# Sweet4x4_02.net
KiCad netlist of a schematic drawn in Altium Designer
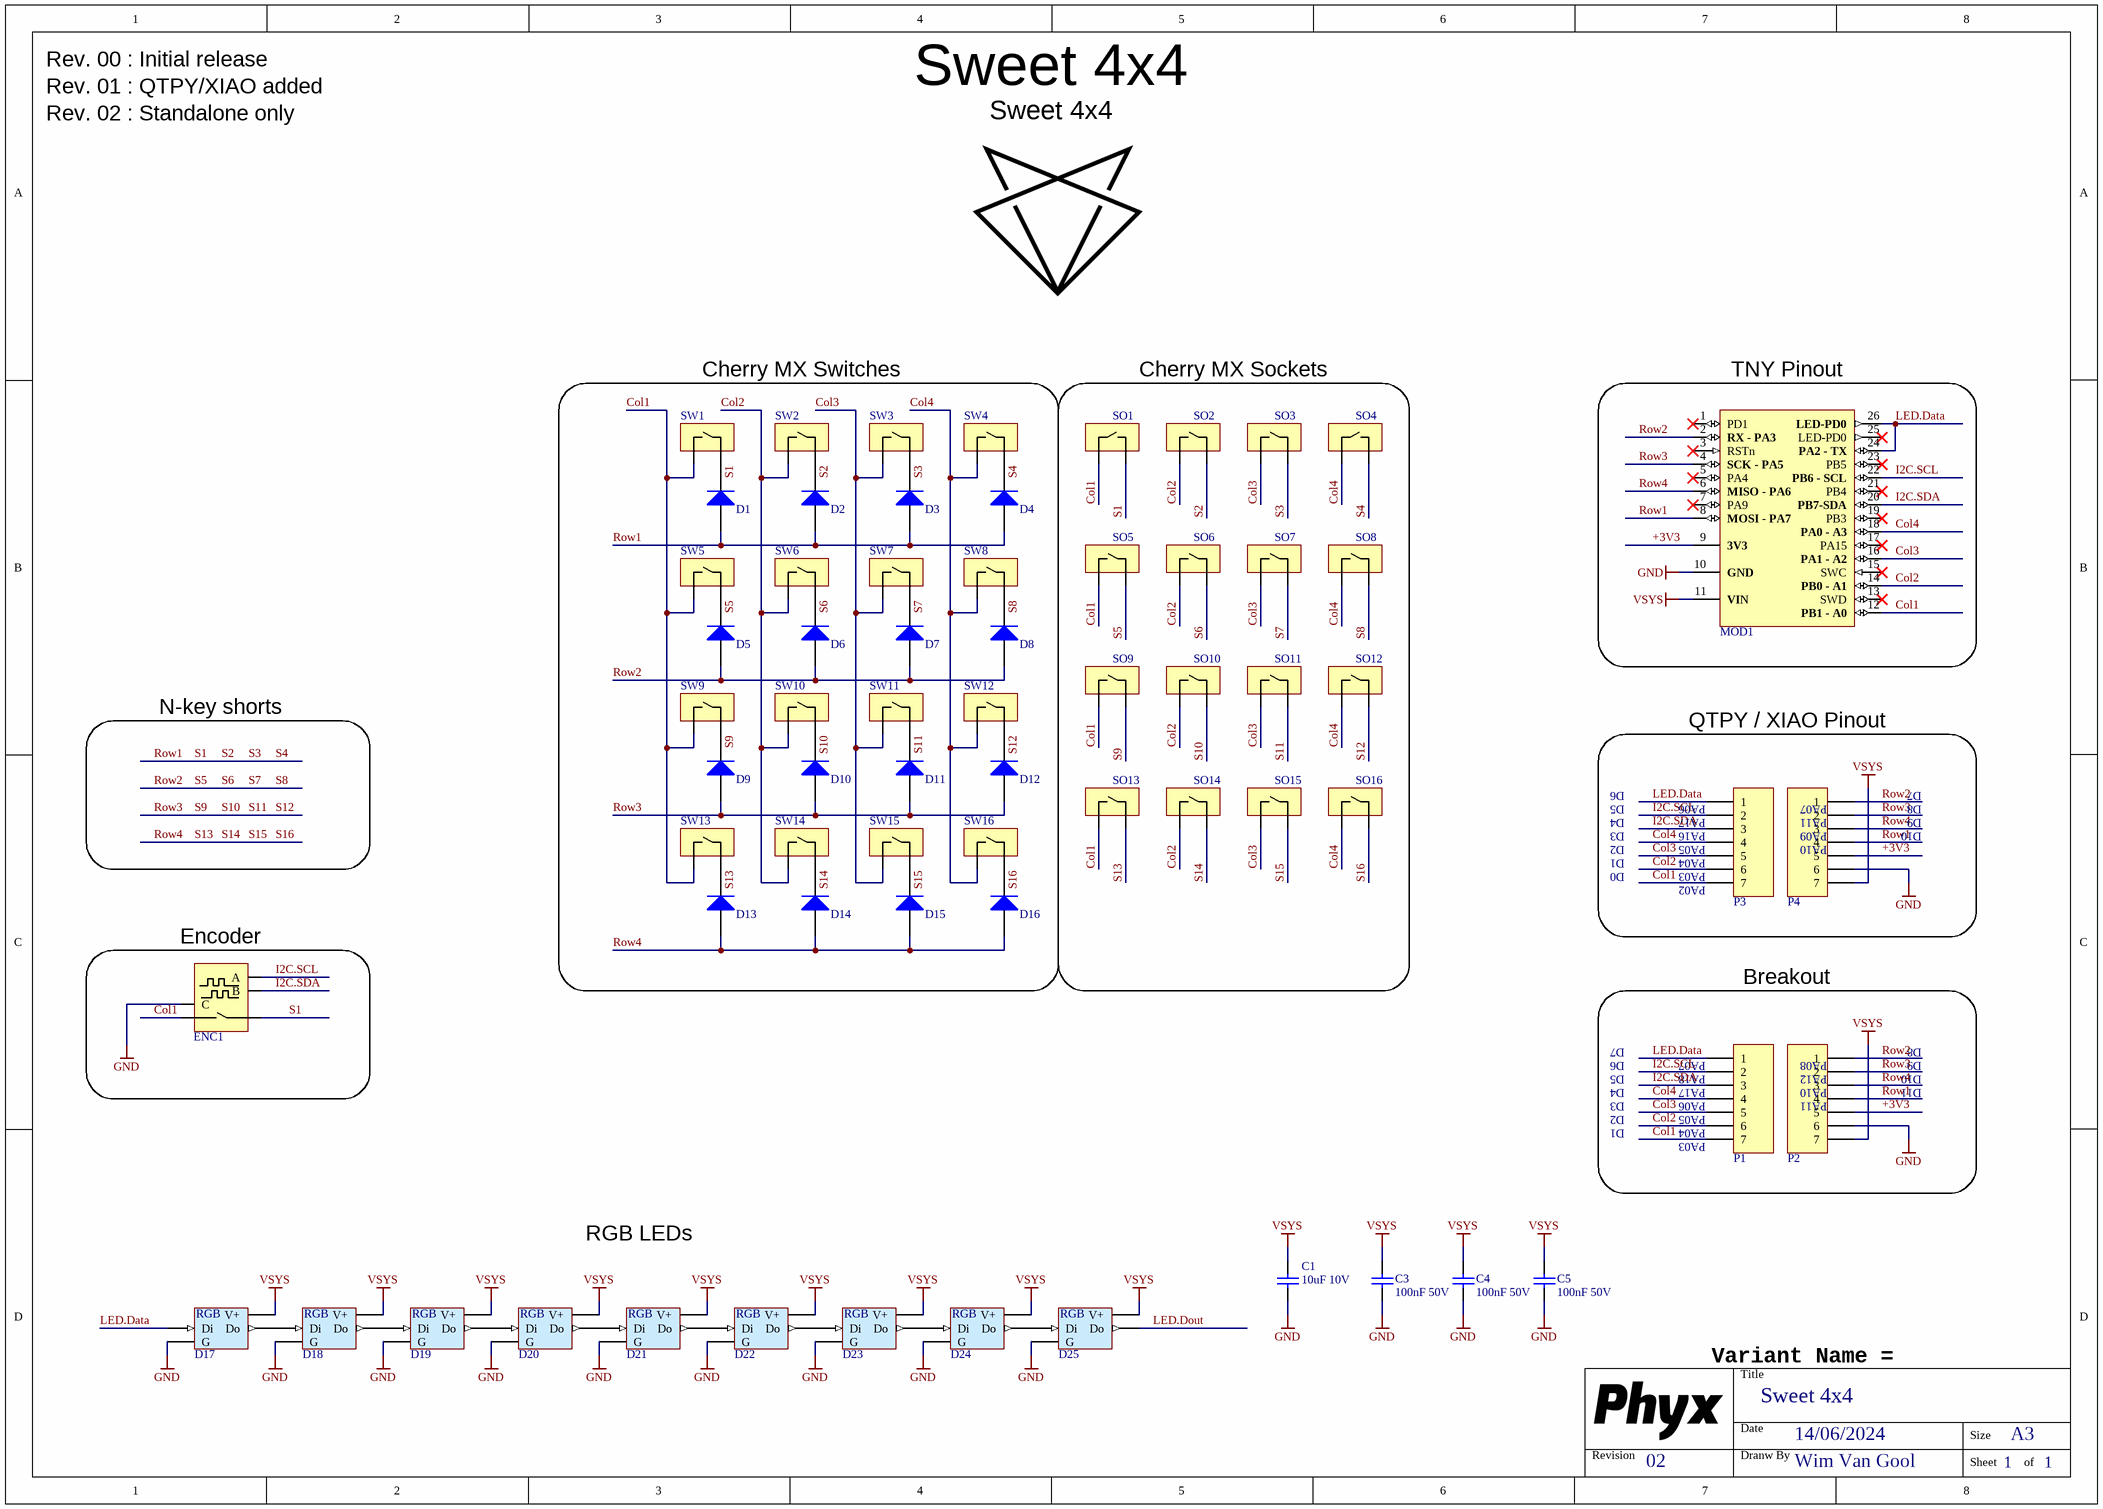
[diagram p0: Sweet4x4_02.SchDoc]

(export (version "E")
  (design (tool "Eeschema 10.0.6"))
  (components
    (comp (ref "C1")
      (value "10uF 10V")
      (footprint "C0805_N")
      (description "Capacitor Ceramic")
      (fields (field (name "Comment") "CAP_CERAMIC"))
      (libsource (lib "Phyx_Components") (part "CAP_CERAMIC"))
    )
    (comp (ref "C3")
      (value "100nF 50V")
      (footprint "C_5.08mm")
      (description "Capacitor Ceramic")
      (fields (field (name "Comment") "CAP_CERAMIC"))
      (libsource (lib "Phyx_Components") (part "CAP_CERAMIC"))
    )
    (comp (ref "C4")
      (value "100nF 50V")
      (footprint "C_5.08mm")
      (description "Capacitor Ceramic")
      (fields (field (name "Comment") "CAP_CERAMIC"))
      (libsource (lib "Phyx_Components") (part "CAP_CERAMIC"))
    )
    (comp (ref "C5")
      (value "100nF 50V")
      (footprint "C_5.08mm")
      (description "Capacitor Ceramic")
      (fields (field (name "Comment") "CAP_CERAMIC"))
      (libsource (lib "Phyx_Components") (part "CAP_CERAMIC"))
    )
    (comp (ref "D1")
      (value "1N4148 100V 200mA 1Vf@10mA")
      (footprint "DO-35")
      (description "Default Diode")
      (libsource (lib "Phyx_Components") (part "DIODE_AC"))
    )
    (comp (ref "D2")
      (value "1N4148 100V 200mA 1Vf@10mA")
      (footprint "DO-35")
      (description "Default Diode")
      (libsource (lib "Phyx_Components") (part "DIODE_AC"))
    )
    (comp (ref "D3")
      (value "1N4148 100V 200mA 1Vf@10mA")
      (footprint "DO-35")
      (description "Default Diode")
      (libsource (lib "Phyx_Components") (part "DIODE_AC"))
    )
    (comp (ref "D4")
      (value "1N4148 100V 200mA 1Vf@10mA")
      (footprint "DO-35")
      (description "Default Diode")
      (libsource (lib "Phyx_Components") (part "DIODE_AC"))
    )
    (comp (ref "D5")
      (value "1N4148 100V 200mA 1Vf@10mA")
      (footprint "DO-35")
      (description "Default Diode")
      (libsource (lib "Phyx_Components") (part "DIODE_AC"))
    )
    (comp (ref "D6")
      (value "1N4148 100V 200mA 1Vf@10mA")
      (footprint "DO-35")
      (description "Default Diode")
      (libsource (lib "Phyx_Components") (part "DIODE_AC"))
    )
    (comp (ref "D7")
      (value "1N4148 100V 200mA 1Vf@10mA")
      (footprint "DO-35")
      (description "Default Diode")
      (libsource (lib "Phyx_Components") (part "DIODE_AC"))
    )
    (comp (ref "D8")
      (value "1N4148 100V 200mA 1Vf@10mA")
      (footprint "DO-35")
      (description "Default Diode")
      (libsource (lib "Phyx_Components") (part "DIODE_AC"))
    )
    (comp (ref "D9")
      (value "1N4148 100V 200mA 1Vf@10mA")
      (footprint "DO-35")
      (description "Default Diode")
      (libsource (lib "Phyx_Components") (part "DIODE_AC"))
    )
    (comp (ref "D10")
      (value "1N4148 100V 200mA 1Vf@10mA")
      (footprint "DO-35")
      (description "Default Diode")
      (libsource (lib "Phyx_Components") (part "DIODE_AC"))
    )
    (comp (ref "D11")
      (value "1N4148 100V 200mA 1Vf@10mA")
      (footprint "DO-35")
      (description "Default Diode")
      (libsource (lib "Phyx_Components") (part "DIODE_AC"))
    )
    (comp (ref "D12")
      (value "1N4148 100V 200mA 1Vf@10mA")
      (footprint "DO-35")
      (description "Default Diode")
      (libsource (lib "Phyx_Components") (part "DIODE_AC"))
    )
    (comp (ref "D13")
      (value "1N4148 100V 200mA 1Vf@10mA")
      (footprint "DO-35")
      (description "Default Diode")
      (libsource (lib "Phyx_Components") (part "DIODE_AC"))
    )
    (comp (ref "D14")
      (value "1N4148 100V 200mA 1Vf@10mA")
      (footprint "DO-35")
      (description "Default Diode")
      (libsource (lib "Phyx_Components") (part "DIODE_AC"))
    )
    (comp (ref "D15")
      (value "1N4148 100V 200mA 1Vf@10mA")
      (footprint "DO-35")
      (description "Default Diode")
      (libsource (lib "Phyx_Components") (part "DIODE_AC"))
    )
    (comp (ref "D16")
      (value "1N4148 100V 200mA 1Vf@10mA")
      (footprint "DO-35")
      (description "Default Diode")
      (libsource (lib "Phyx_Components") (part "DIODE_AC"))
    )
    (comp (ref "D17")
      (value "WS2812 based digital RGB LED 5mm Rectangle")
      (footprint "LED_5mm_RGB_RECT_EASY")
      (description "LED RGB WS2812 5mm Rectangle")
      (libsource (lib "Phyx_Components") (part "LED_RGB_WS2812B_5mm"))
    )
    (comp (ref "D18")
      (value "WS2812 based digital RGB LED 5mm Rectangle")
      (footprint "LED_5mm_RGB_RECT_EASY")
      (description "LED RGB WS2812 5mm Rectangle")
      (libsource (lib "Phyx_Components") (part "LED_RGB_WS2812B_5mm"))
    )
    (comp (ref "D19")
      (value "WS2812 based digital RGB LED 5mm Rectangle")
      (footprint "LED_5mm_RGB_RECT_EASY")
      (description "LED RGB WS2812 5mm Rectangle")
      (libsource (lib "Phyx_Components") (part "LED_RGB_WS2812B_5mm"))
    )
    (comp (ref "D20")
      (value "WS2812 based digital RGB LED 5mm Rectangle")
      (footprint "LED_5mm_RGB_RECT_EASY")
      (description "LED RGB WS2812 5mm Rectangle")
      (libsource (lib "Phyx_Components") (part "LED_RGB_WS2812B_5mm"))
    )
    (comp (ref "D21")
      (value "WS2812 based digital RGB LED 5mm Rectangle")
      (footprint "LED_5mm_RGB_RECT_EASY")
      (description "LED RGB WS2812 5mm Rectangle")
      (libsource (lib "Phyx_Components") (part "LED_RGB_WS2812B_5mm"))
    )
    (comp (ref "D22")
      (value "WS2812 based digital RGB LED 5mm Rectangle")
      (footprint "LED_5mm_RGB_RECT_EASY")
      (description "LED RGB WS2812 5mm Rectangle")
      (libsource (lib "Phyx_Components") (part "LED_RGB_WS2812B_5mm"))
    )
    (comp (ref "D23")
      (value "WS2812 based digital RGB LED 5mm Rectangle")
      (footprint "LED_5mm_RGB_RECT_EASY")
      (description "LED RGB WS2812 5mm Rectangle")
      (libsource (lib "Phyx_Components") (part "LED_RGB_WS2812B_5mm"))
    )
    (comp (ref "D24")
      (value "WS2812 based digital RGB LED 5mm Rectangle")
      (footprint "LED_5mm_RGB_RECT_EASY")
      (description "LED RGB WS2812 5mm Rectangle")
      (libsource (lib "Phyx_Components") (part "LED_RGB_WS2812B_5mm"))
    )
    (comp (ref "D25")
      (value "WS2812 based digital RGB LED 5mm Rectangle")
      (footprint "LED_5mm_RGB_RECT_EASY")
      (description "LED RGB WS2812 5mm Rectangle")
      (libsource (lib "Phyx_Components") (part "LED_RGB_WS2812B_5mm"))
    )
    (comp (ref "ENC1")
      (value "Rotary Encoder with Switch")
      (footprint "PEC11-4215F-S0024")
      (libsource (lib "Phyx_Components") (part "ROT_ENC_3P_SW"))
    )
    (comp (ref "MOD1")
      (value "CH23V203 based TNY module")
      (footprint "PHYX_LANA_TNY_SMD")
      (libsource (lib "Phyx_Components") (part "PHYX_LANA_TNY_SMD"))
    )
    (comp (ref "P1") (value "Header 7") (footprint "HDR1X7") (libsource (lib "") (part "Header 7_1")))
    (comp (ref "P2")
      (value "Header 7")
      (footprint "HDR1X7")
      (libsource (lib "Phyx_Components") (part "Header 7"))
    )
    (comp (ref "P3") (value "Header 7") (footprint "HDR1X7") (libsource (lib "") (part "Header 7_1")))
    (comp (ref "P4")
      (value "Header 7")
      (footprint "HDR1X7")
      (libsource (lib "Phyx_Components") (part "Header 7"))
    )
    (comp (ref "SO1")
      (value "Kailh MX Socket")
      (footprint "Kailh_MX_Socket")
      (libsource (lib "Phyx_Components") (part "SW_TACT"))
    )
    (comp (ref "SO2")
      (value "Kailh MX Socket")
      (footprint "Kailh_MX_Socket")
      (libsource (lib "") (part "SW_TACT_1"))
    )
    (comp (ref "SO3")
      (value "Kailh MX Socket")
      (footprint "Kailh_MX_Socket")
      (libsource (lib "") (part "SW_TACT_1"))
    )
    (comp (ref "SO4")
      (value "Kailh MX Socket")
      (footprint "Kailh_MX_Socket")
      (libsource (lib "Phyx_Components") (part "SW_TACT"))
    )
    (comp (ref "SO5")
      (value "Kailh MX Socket")
      (footprint "Kailh_MX_Socket")
      (libsource (lib "") (part "SW_TACT_1"))
    )
    (comp (ref "SO6")
      (value "Kailh MX Socket")
      (footprint "Kailh_MX_Socket")
      (libsource (lib "") (part "SW_TACT_1"))
    )
    (comp (ref "SO7")
      (value "Kailh MX Socket")
      (footprint "Kailh_MX_Socket")
      (libsource (lib "") (part "SW_TACT_1"))
    )
    (comp (ref "SO8")
      (value "Kailh MX Socket")
      (footprint "Kailh_MX_Socket")
      (libsource (lib "") (part "SW_TACT_1"))
    )
    (comp (ref "SO9")
      (value "Kailh MX Socket")
      (footprint "Kailh_MX_Socket")
      (libsource (lib "") (part "SW_TACT_1"))
    )
    (comp (ref "SO10")
      (value "Kailh MX Socket")
      (footprint "Kailh_MX_Socket")
      (libsource (lib "") (part "SW_TACT_1"))
    )
    (comp (ref "SO11")
      (value "Kailh MX Socket")
      (footprint "Kailh_MX_Socket")
      (libsource (lib "") (part "SW_TACT_1"))
    )
    (comp (ref "SO12")
      (value "Kailh MX Socket")
      (footprint "Kailh_MX_Socket")
      (libsource (lib "") (part "SW_TACT_1"))
    )
    (comp (ref "SO13")
      (value "Kailh MX Socket")
      (footprint "Kailh_MX_Socket")
      (libsource (lib "") (part "SW_TACT_1"))
    )
    (comp (ref "SO14")
      (value "Kailh MX Socket")
      (footprint "Kailh_MX_Socket")
      (libsource (lib "") (part "SW_TACT_1"))
    )
    (comp (ref "SO15")
      (value "Kailh MX Socket")
      (footprint "Kailh_MX_Socket")
      (libsource (lib "") (part "SW_TACT_1"))
    )
    (comp (ref "SO16")
      (value "Kailh MX Socket")
      (footprint "Kailh_MX_Socket")
      (libsource (lib "") (part "SW_TACT_1"))
    )
    (comp (ref "SW1")
      (value "Cherry MX Blue")
      (footprint "Cherry_MX1A")
      (libsource (lib "") (part "SW_TACT_1"))
    )
    (comp (ref "SW2")
      (value "Cherry MX Blue")
      (footprint "Cherry_MX1A")
      (libsource (lib "") (part "SW_TACT_1"))
    )
    (comp (ref "SW3")
      (value "Cherry MX Blue")
      (footprint "Cherry_MX1A")
      (libsource (lib "") (part "SW_TACT_1"))
    )
    (comp (ref "SW4")
      (value "Cherry MX Blue")
      (footprint "Cherry_MX1A")
      (libsource (lib "") (part "SW_TACT_1"))
    )
    (comp (ref "SW5")
      (value "Cherry MX Blue")
      (footprint "Cherry_MX1A")
      (libsource (lib "") (part "SW_TACT_1"))
    )
    (comp (ref "SW6")
      (value "Cherry MX Blue")
      (footprint "Cherry_MX1A")
      (libsource (lib "") (part "SW_TACT_1"))
    )
    (comp (ref "SW7")
      (value "Cherry MX Blue")
      (footprint "Cherry_MX1A")
      (libsource (lib "") (part "SW_TACT_1"))
    )
    (comp (ref "SW8")
      (value "Cherry MX Blue")
      (footprint "Cherry_MX1A")
      (libsource (lib "") (part "SW_TACT_1"))
    )
    (comp (ref "SW9")
      (value "Cherry MX Blue")
      (footprint "Cherry_MX1A")
      (libsource (lib "") (part "SW_TACT_1"))
    )
    (comp (ref "SW10")
      (value "Cherry MX Blue")
      (footprint "Cherry_MX1A")
      (libsource (lib "") (part "SW_TACT_1"))
    )
    (comp (ref "SW11")
      (value "Cherry MX Blue")
      (footprint "Cherry_MX1A")
      (libsource (lib "") (part "SW_TACT_1"))
    )
    (comp (ref "SW12")
      (value "Cherry MX Blue")
      (footprint "Cherry_MX1A")
      (libsource (lib "") (part "SW_TACT_1"))
    )
    (comp (ref "SW13")
      (value "Cherry MX Blue")
      (footprint "Cherry_MX1A")
      (libsource (lib "") (part "SW_TACT_1"))
    )
    (comp (ref "SW14")
      (value "Cherry MX Blue")
      (footprint "Cherry_MX1A")
      (libsource (lib "") (part "SW_TACT_1"))
    )
    (comp (ref "SW15")
      (value "Cherry MX Blue")
      (footprint "Cherry_MX1A")
      (libsource (lib "") (part "SW_TACT_1"))
    )
    (comp (ref "SW16")
      (value "Cherry MX Blue")
      (footprint "Cherry_MX1A")
      (libsource (lib "") (part "SW_TACT_1"))
    )
  )
  (nets
    (net (code "1") (name "/+3V3") (class "Default")
      (node (ref "MOD1") (pin "9") (pinfunction "3V3_9") (pintype "power_in"))
      (node (ref "P2") (pin "5") (pinfunction "5_5") (pintype "passive"))
      (node (ref "P4") (pin "5") (pinfunction "5_5") (pintype "passive"))
    )
    (net (code "2") (name "/Col1") (class "Default")
      (node (ref "ENC1") (pin "1") (pinfunction "1_1") (pintype "passive"))
      (node (ref "MOD1") (pin "12") (pinfunction "PB1_-_A0_12") (pintype "bidirectional"))
      (node (ref "P1") (pin "7") (pinfunction "7_7") (pintype "passive"))
      (node (ref "P3") (pin "7") (pinfunction "7_7") (pintype "passive"))
      (node (ref "SO1") (pin "2") (pinfunction "2_2") (pintype "passive"))
      (node (ref "SO13") (pin "1") (pinfunction "1_1") (pintype "passive"))
      (node (ref "SO5") (pin "1") (pinfunction "1_1") (pintype "passive"))
      (node (ref "SO9") (pin "1") (pinfunction "1_1") (pintype "passive"))
      (node (ref "SW1") (pin "1") (pinfunction "1_1") (pintype "passive"))
      (node (ref "SW13") (pin "1") (pinfunction "1_1") (pintype "passive"))
      (node (ref "SW5") (pin "1") (pinfunction "1_1") (pintype "passive"))
      (node (ref "SW9") (pin "1") (pinfunction "1_1") (pintype "passive"))
    )
    (net (code "3") (name "/Col2") (class "Default")
      (node (ref "MOD1") (pin "14") (pinfunction "PB0_-_A1_14") (pintype "bidirectional"))
      (node (ref "P1") (pin "6") (pinfunction "6_6") (pintype "passive"))
      (node (ref "P3") (pin "6") (pinfunction "6_6") (pintype "passive"))
      (node (ref "SO10") (pin "1") (pinfunction "1_1") (pintype "passive"))
      (node (ref "SO14") (pin "1") (pinfunction "1_1") (pintype "passive"))
      (node (ref "SO2") (pin "1") (pinfunction "1_1") (pintype "passive"))
      (node (ref "SO6") (pin "1") (pinfunction "1_1") (pintype "passive"))
      (node (ref "SW10") (pin "1") (pinfunction "1_1") (pintype "passive"))
      (node (ref "SW14") (pin "1") (pinfunction "1_1") (pintype "passive"))
      (node (ref "SW2") (pin "1") (pinfunction "1_1") (pintype "passive"))
      (node (ref "SW6") (pin "1") (pinfunction "1_1") (pintype "passive"))
    )
    (net (code "4") (name "/Col3") (class "Default")
      (node (ref "MOD1") (pin "16") (pinfunction "PA1_-_A2_16") (pintype "bidirectional"))
      (node (ref "P1") (pin "5") (pinfunction "5_5") (pintype "passive"))
      (node (ref "P3") (pin "5") (pinfunction "5_5") (pintype "passive"))
      (node (ref "SO11") (pin "1") (pinfunction "1_1") (pintype "passive"))
      (node (ref "SO15") (pin "1") (pinfunction "1_1") (pintype "passive"))
      (node (ref "SO3") (pin "1") (pinfunction "1_1") (pintype "passive"))
      (node (ref "SO7") (pin "1") (pinfunction "1_1") (pintype "passive"))
      (node (ref "SW11") (pin "1") (pinfunction "1_1") (pintype "passive"))
      (node (ref "SW15") (pin "1") (pinfunction "1_1") (pintype "passive"))
      (node (ref "SW3") (pin "1") (pinfunction "1_1") (pintype "passive"))
      (node (ref "SW7") (pin "1") (pinfunction "1_1") (pintype "passive"))
    )
    (net (code "5") (name "/Col4") (class "Default")
      (node (ref "MOD1") (pin "18") (pinfunction "PA0_-_A3_18") (pintype "bidirectional"))
      (node (ref "P1") (pin "4") (pinfunction "4_4") (pintype "passive"))
      (node (ref "P3") (pin "4") (pinfunction "4_4") (pintype "passive"))
      (node (ref "SO12") (pin "1") (pinfunction "1_1") (pintype "passive"))
      (node (ref "SO16") (pin "1") (pinfunction "1_1") (pintype "passive"))
      (node (ref "SO4") (pin "2") (pinfunction "2_2") (pintype "passive"))
      (node (ref "SO8") (pin "1") (pinfunction "1_1") (pintype "passive"))
      (node (ref "SW12") (pin "1") (pinfunction "1_1") (pintype "passive"))
      (node (ref "SW16") (pin "1") (pinfunction "1_1") (pintype "passive"))
      (node (ref "SW4") (pin "1") (pinfunction "1_1") (pintype "passive"))
      (node (ref "SW8") (pin "1") (pinfunction "1_1") (pintype "passive"))
    )
    (net (code "6") (name "/I2C.SCL") (class "Default")
      (node (ref "ENC1") (pin "A") (pinfunction "A_A") (pintype "passive"))
      (node (ref "MOD1") (pin "22") (pinfunction "PB6_-_SCL_22") (pintype "bidirectional"))
      (node (ref "P1") (pin "2") (pinfunction "2_2") (pintype "passive"))
      (node (ref "P3") (pin "2") (pinfunction "2_2") (pintype "passive"))
    )
    (net (code "7") (name "/I2C.SDA") (class "Default")
      (node (ref "ENC1") (pin "B") (pinfunction "B_B") (pintype "passive"))
      (node (ref "MOD1") (pin "20") (pinfunction "PB7-SDA_20") (pintype "bidirectional"))
      (node (ref "P1") (pin "3") (pinfunction "3_3") (pintype "passive"))
      (node (ref "P3") (pin "3") (pinfunction "3_3") (pintype "passive"))
    )
    (net (code "8") (name "/LED.Data") (class "Default")
      (node (ref "D17") (pin "4") (pinfunction "Di_4") (pintype "input"))
      (node (ref "MOD1") (pin "24") (pinfunction "PA2_-_TX_24") (pintype "bidirectional"))
      (node (ref "MOD1") (pin "26") (pinfunction "LED-PD0_26") (pintype "output"))
      (node (ref "P1") (pin "1") (pinfunction "1_1") (pintype "passive"))
      (node (ref "P3") (pin "1") (pinfunction "1_1") (pintype "passive"))
    )
    (net (code "9") (name "/LED.Dout") (class "Default")
      (node (ref "D25") (pin "1") (pinfunction "Do_1") (pintype "output"))
    )
    (net (code "10") (name "/Row1") (class "Default")
      (node (ref "D1") (pin "A") (pinfunction "A_A") (pintype "passive"))
      (node (ref "D1") (pin "C") (pinfunction "C_C") (pintype "passive"))
      (node (ref "D2") (pin "A") (pinfunction "A_A") (pintype "passive"))
      (node (ref "D2") (pin "C") (pinfunction "C_C") (pintype "passive"))
      (node (ref "D3") (pin "A") (pinfunction "A_A") (pintype "passive"))
      (node (ref "D3") (pin "C") (pinfunction "C_C") (pintype "passive"))
      (node (ref "D4") (pin "A") (pinfunction "A_A") (pintype "passive"))
      (node (ref "D4") (pin "C") (pinfunction "C_C") (pintype "passive"))
      (node (ref "ENC1") (pin "2") (pinfunction "2_2") (pintype "passive"))
      (node (ref "MOD1") (pin "8") (pinfunction "MOSI_-_PA7_8") (pintype "bidirectional"))
      (node (ref "P2") (pin "4") (pinfunction "4_4") (pintype "passive"))
      (node (ref "P4") (pin "4") (pinfunction "4_4") (pintype "passive"))
      (node (ref "SO1") (pin "1") (pinfunction "1_1") (pintype "passive"))
      (node (ref "SO2") (pin "2") (pinfunction "2_2") (pintype "passive"))
      (node (ref "SO3") (pin "2") (pinfunction "2_2") (pintype "passive"))
      (node (ref "SO4") (pin "1") (pinfunction "1_1") (pintype "passive"))
      (node (ref "SW1") (pin "2") (pinfunction "2_2") (pintype "passive"))
      (node (ref "SW2") (pin "2") (pinfunction "2_2") (pintype "passive"))
      (node (ref "SW3") (pin "2") (pinfunction "2_2") (pintype "passive"))
      (node (ref "SW4") (pin "2") (pinfunction "2_2") (pintype "passive"))
    )
    (net (code "11") (name "/Row2") (class "Default")
      (node (ref "D5") (pin "A") (pinfunction "A_A") (pintype "passive"))
      (node (ref "D5") (pin "C") (pinfunction "C_C") (pintype "passive"))
      (node (ref "D6") (pin "A") (pinfunction "A_A") (pintype "passive"))
      (node (ref "D6") (pin "C") (pinfunction "C_C") (pintype "passive"))
      (node (ref "D7") (pin "A") (pinfunction "A_A") (pintype "passive"))
      (node (ref "D7") (pin "C") (pinfunction "C_C") (pintype "passive"))
      (node (ref "D8") (pin "A") (pinfunction "A_A") (pintype "passive"))
      (node (ref "D8") (pin "C") (pinfunction "C_C") (pintype "passive"))
      (node (ref "MOD1") (pin "2") (pinfunction "RX_-_PA3_2") (pintype "bidirectional"))
      (node (ref "P2") (pin "1") (pinfunction "1_1") (pintype "passive"))
      (node (ref "P4") (pin "1") (pinfunction "1_1") (pintype "passive"))
      (node (ref "SO5") (pin "2") (pinfunction "2_2") (pintype "passive"))
      (node (ref "SO6") (pin "2") (pinfunction "2_2") (pintype "passive"))
      (node (ref "SO7") (pin "2") (pinfunction "2_2") (pintype "passive"))
      (node (ref "SO8") (pin "2") (pinfunction "2_2") (pintype "passive"))
      (node (ref "SW5") (pin "2") (pinfunction "2_2") (pintype "passive"))
      (node (ref "SW6") (pin "2") (pinfunction "2_2") (pintype "passive"))
      (node (ref "SW7") (pin "2") (pinfunction "2_2") (pintype "passive"))
      (node (ref "SW8") (pin "2") (pinfunction "2_2") (pintype "passive"))
    )
    (net (code "12") (name "/Row3") (class "Default")
      (node (ref "D10") (pin "A") (pinfunction "A_A") (pintype "passive"))
      (node (ref "D10") (pin "C") (pinfunction "C_C") (pintype "passive"))
      (node (ref "D11") (pin "A") (pinfunction "A_A") (pintype "passive"))
      (node (ref "D11") (pin "C") (pinfunction "C_C") (pintype "passive"))
      (node (ref "D12") (pin "A") (pinfunction "A_A") (pintype "passive"))
      (node (ref "D12") (pin "C") (pinfunction "C_C") (pintype "passive"))
      (node (ref "D9") (pin "A") (pinfunction "A_A") (pintype "passive"))
      (node (ref "D9") (pin "C") (pinfunction "C_C") (pintype "passive"))
      (node (ref "MOD1") (pin "4") (pinfunction "SCK_-_PA5_4") (pintype "bidirectional"))
      (node (ref "P2") (pin "2") (pinfunction "2_2") (pintype "passive"))
      (node (ref "P4") (pin "2") (pinfunction "2_2") (pintype "passive"))
      (node (ref "SO10") (pin "2") (pinfunction "2_2") (pintype "passive"))
      (node (ref "SO11") (pin "2") (pinfunction "2_2") (pintype "passive"))
      (node (ref "SO12") (pin "2") (pinfunction "2_2") (pintype "passive"))
      (node (ref "SO9") (pin "2") (pinfunction "2_2") (pintype "passive"))
      (node (ref "SW10") (pin "2") (pinfunction "2_2") (pintype "passive"))
      (node (ref "SW11") (pin "2") (pinfunction "2_2") (pintype "passive"))
      (node (ref "SW12") (pin "2") (pinfunction "2_2") (pintype "passive"))
      (node (ref "SW9") (pin "2") (pinfunction "2_2") (pintype "passive"))
    )
    (net (code "13") (name "/Row4") (class "Default")
      (node (ref "D13") (pin "A") (pinfunction "A_A") (pintype "passive"))
      (node (ref "D13") (pin "C") (pinfunction "C_C") (pintype "passive"))
      (node (ref "D14") (pin "A") (pinfunction "A_A") (pintype "passive"))
      (node (ref "D14") (pin "C") (pinfunction "C_C") (pintype "passive"))
      (node (ref "D15") (pin "A") (pinfunction "A_A") (pintype "passive"))
      (node (ref "D15") (pin "C") (pinfunction "C_C") (pintype "passive"))
      (node (ref "D16") (pin "A") (pinfunction "A_A") (pintype "passive"))
      (node (ref "D16") (pin "C") (pinfunction "C_C") (pintype "passive"))
      (node (ref "MOD1") (pin "6") (pinfunction "MISO_-_PA6_6") (pintype "bidirectional"))
      (node (ref "P2") (pin "3") (pinfunction "3_3") (pintype "passive"))
      (node (ref "P4") (pin "3") (pinfunction "3_3") (pintype "passive"))
      (node (ref "SO13") (pin "2") (pinfunction "2_2") (pintype "passive"))
      (node (ref "SO14") (pin "2") (pinfunction "2_2") (pintype "passive"))
      (node (ref "SO15") (pin "2") (pinfunction "2_2") (pintype "passive"))
      (node (ref "SO16") (pin "2") (pinfunction "2_2") (pintype "passive"))
      (node (ref "SW13") (pin "2") (pinfunction "2_2") (pintype "passive"))
      (node (ref "SW14") (pin "2") (pinfunction "2_2") (pintype "passive"))
      (node (ref "SW15") (pin "2") (pinfunction "2_2") (pintype "passive"))
      (node (ref "SW16") (pin "2") (pinfunction "2_2") (pintype "passive"))
    )
    (net (code "14") (name "GND") (class "Default")
      (node (ref "C1") (pin "2") (pinfunction "2_2") (pintype "passive"))
      (node (ref "C3") (pin "2") (pinfunction "2_2") (pintype "passive"))
      (node (ref "C4") (pin "2") (pinfunction "2_2") (pintype "passive"))
      (node (ref "C5") (pin "2") (pinfunction "2_2") (pintype "passive"))
      (node (ref "D17") (pin "3") (pinfunction "G_3") (pintype "power_in"))
      (node (ref "D18") (pin "3") (pinfunction "G_3") (pintype "power_in"))
      (node (ref "D19") (pin "3") (pinfunction "G_3") (pintype "power_in"))
      (node (ref "D20") (pin "3") (pinfunction "G_3") (pintype "power_in"))
      (node (ref "D21") (pin "3") (pinfunction "G_3") (pintype "power_in"))
      (node (ref "D22") (pin "3") (pinfunction "G_3") (pintype "power_in"))
      (node (ref "D23") (pin "3") (pinfunction "G_3") (pintype "power_in"))
      (node (ref "D24") (pin "3") (pinfunction "G_3") (pintype "power_in"))
      (node (ref "D25") (pin "3") (pinfunction "G_3") (pintype "power_in"))
      (node (ref "ENC1") (pin "C") (pinfunction "C_C") (pintype "passive"))
      (node (ref "MOD1") (pin "10") (pinfunction "GND_10") (pintype "power_in"))
      (node (ref "P2") (pin "6") (pinfunction "6_6") (pintype "passive"))
      (node (ref "P4") (pin "6") (pinfunction "6_6") (pintype "passive"))
    )
    (net (code "15") (name "Net-(D17-Do)") (class "Default")
      (node (ref "D17") (pin "1") (pinfunction "Do_1") (pintype "output"))
      (node (ref "D18") (pin "4") (pinfunction "Di_4") (pintype "input"))
    )
    (net (code "16") (name "Net-(D18-Do)") (class "Default")
      (node (ref "D18") (pin "1") (pinfunction "Do_1") (pintype "output"))
      (node (ref "D19") (pin "4") (pinfunction "Di_4") (pintype "input"))
    )
    (net (code "17") (name "Net-(D19-Do)") (class "Default")
      (node (ref "D19") (pin "1") (pinfunction "Do_1") (pintype "output"))
      (node (ref "D20") (pin "4") (pinfunction "Di_4") (pintype "input"))
    )
    (net (code "18") (name "Net-(D20-Do)") (class "Default")
      (node (ref "D20") (pin "1") (pinfunction "Do_1") (pintype "output"))
      (node (ref "D21") (pin "4") (pinfunction "Di_4") (pintype "input"))
    )
    (net (code "19") (name "Net-(D21-Do)") (class "Default")
      (node (ref "D21") (pin "1") (pinfunction "Do_1") (pintype "output"))
      (node (ref "D22") (pin "4") (pinfunction "Di_4") (pintype "input"))
    )
    (net (code "20") (name "Net-(D22-Do)") (class "Default")
      (node (ref "D22") (pin "1") (pinfunction "Do_1") (pintype "output"))
      (node (ref "D23") (pin "4") (pinfunction "Di_4") (pintype "input"))
    )
    (net (code "21") (name "Net-(D23-Do)") (class "Default")
      (node (ref "D23") (pin "1") (pinfunction "Do_1") (pintype "output"))
      (node (ref "D24") (pin "4") (pinfunction "Di_4") (pintype "input"))
    )
    (net (code "22") (name "Net-(D24-Do)") (class "Default")
      (node (ref "D24") (pin "1") (pinfunction "Do_1") (pintype "output"))
      (node (ref "D25") (pin "4") (pinfunction "Di_4") (pintype "input"))
    )
    (net (code "23") (name "VSYS") (class "Default")
      (node (ref "C1") (pin "1") (pinfunction "1_1") (pintype "passive"))
      (node (ref "C3") (pin "1") (pinfunction "1_1") (pintype "passive"))
      (node (ref "C4") (pin "1") (pinfunction "1_1") (pintype "passive"))
      (node (ref "C5") (pin "1") (pinfunction "1_1") (pintype "passive"))
      (node (ref "D17") (pin "2") (pinfunction "V+_2") (pintype "power_in"))
      (node (ref "D18") (pin "2") (pinfunction "V+_2") (pintype "power_in"))
      (node (ref "D19") (pin "2") (pinfunction "V+_2") (pintype "power_in"))
      (node (ref "D20") (pin "2") (pinfunction "V+_2") (pintype "power_in"))
      (node (ref "D21") (pin "2") (pinfunction "V+_2") (pintype "power_in"))
      (node (ref "D22") (pin "2") (pinfunction "V+_2") (pintype "power_in"))
      (node (ref "D23") (pin "2") (pinfunction "V+_2") (pintype "power_in"))
      (node (ref "D24") (pin "2") (pinfunction "V+_2") (pintype "power_in"))
      (node (ref "D25") (pin "2") (pinfunction "V+_2") (pintype "power_in"))
      (node (ref "MOD1") (pin "11") (pinfunction "VIN_11") (pintype "power_in"))
      (node (ref "P2") (pin "7") (pinfunction "7_7") (pintype "passive"))
      (node (ref "P4") (pin "7") (pinfunction "7_7") (pintype "passive"))
    )
    (net (code "24") (name "unconnected-(MOD1-LED-PD0-Pad25)") (class "Default")
      (node (ref "MOD1") (pin "25") (pinfunction "LED-PD0_25") (pintype "output+no_connect"))
    )
    (net (code "25") (name "unconnected-(MOD1-PA4-Pad5)") (class "Default")
      (node (ref "MOD1") (pin "5") (pinfunction "PA4_5") (pintype "bidirectional+no_connect"))
    )
    (net (code "26") (name "unconnected-(MOD1-PA9-Pad7)") (class "Default")
      (node (ref "MOD1") (pin "7") (pinfunction "PA9_7") (pintype "bidirectional+no_connect"))
    )
    (net (code "27") (name "unconnected-(MOD1-PA15-Pad17)") (class "Default")
      (node (ref "MOD1") (pin "17") (pinfunction "PA15_17") (pintype "bidirectional+no_connect"))
    )
    (net (code "28") (name "unconnected-(MOD1-PB3-Pad19)") (class "Default")
      (node (ref "MOD1") (pin "19") (pinfunction "PB3_19") (pintype "bidirectional+no_connect"))
    )
    (net (code "29") (name "unconnected-(MOD1-PB4-Pad21)") (class "Default")
      (node (ref "MOD1") (pin "21") (pinfunction "PB4_21") (pintype "bidirectional+no_connect"))
    )
    (net (code "30") (name "unconnected-(MOD1-PB5-Pad23)") (class "Default")
      (node (ref "MOD1") (pin "23") (pinfunction "PB5_23") (pintype "bidirectional+no_connect"))
    )
    (net (code "31") (name "unconnected-(MOD1-PD1-Pad1)") (class "Default")
      (node (ref "MOD1") (pin "1") (pinfunction "PD1_1") (pintype "bidirectional+no_connect"))
    )
    (net (code "32") (name "unconnected-(MOD1-RSTn-Pad3)") (class "Default")
      (node (ref "MOD1") (pin "3") (pinfunction "RSTn_3") (pintype "input+no_connect"))
    )
    (net (code "33") (name "unconnected-(MOD1-SWC-Pad15)") (class "Default")
      (node (ref "MOD1") (pin "15") (pinfunction "SWC_15") (pintype "input+no_connect"))
    )
    (net (code "34") (name "unconnected-(MOD1-SWD-Pad13)") (class "Default")
      (node (ref "MOD1") (pin "13") (pinfunction "SWD_13") (pintype "bidirectional+no_connect"))
    )
  )
)
